# WiFi.net
KiCad netlist of a schematic drawn in Altium Designer
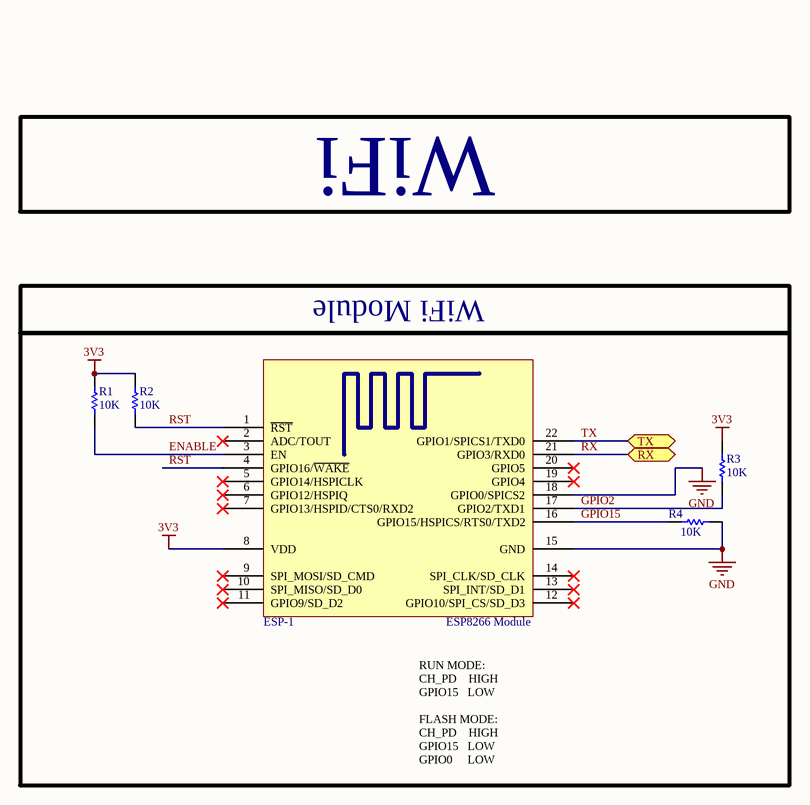
[diagram p0: WiFi.SchDoc]

(export (version "E")
  (design (tool "Eeschema 10.0.6"))
  (components
    (comp (ref "ESP-1")
      (value "ESP8266 Module")
      (footprint "PCBComponent")
      (libsource (lib "BG Vault") (part "ESP-12E-A.4"))
    )
    (comp (ref "R1")
      (value "10K")
      (footprint "RESC0805(2012)_L")
      (description "10K 0.125W 5% 0805 (2012 Metric)  SMD")
      (fields (field (name "POWER") "0.125 W") (field (name "TOLERANCE") "5 %"))
      (libsource (lib "Altium Content Vault") (part "CMP-1013-00098-1"))
    )
    (comp (ref "R2")
      (value "10K")
      (footprint "RESC0805(2012)_L")
      (description "10K 0.125W 5% 0805 (2012 Metric)  SMD")
      (fields (field (name "POWER") "0.125 W") (field (name "TOLERANCE") "5 %"))
      (libsource (lib "Altium Content Vault") (part "CMP-1013-00098-1"))
    )
    (comp (ref "R3")
      (value "10K")
      (footprint "RESC0805(2012)_L")
      (description "10K 0.125W 5% 0805 (2012 Metric)  SMD")
      (fields (field (name "POWER") "0.125 W") (field (name "TOLERANCE") "5 %"))
      (libsource (lib "Altium Content Vault") (part "CMP-1013-00098-1"))
    )
    (comp (ref "R4")
      (value "10K")
      (footprint "RESC0805(2012)_L")
      (description "10K 0.125W 5% 0805 (2012 Metric)  SMD")
      (fields (field (name "POWER") "0.125 W") (field (name "TOLERANCE") "5 %"))
      (libsource (lib "Altium Content Vault") (part "CMP-1013-00098-1"))
    )
  )
  (nets
    (net (code "1") (name "/ENABLE") (class "Default")
      (node (ref "ESP-1") (pin "3") (pinfunction "EN_3") (pintype "passive"))
      (node (ref "R1") (pin "1") (pinfunction "1_1") (pintype "passive"))
    )
    (net (code "2") (name "/GPIO2") (class "Default")
      (node (ref "ESP-1") (pin "17") (pinfunction "GPIO2/TXD1_17") (pintype "passive"))
      (node (ref "R3") (pin "1") (pinfunction "1_1") (pintype "passive"))
    )
    (net (code "3") (name "/GPIO15") (class "Default")
      (node (ref "ESP-1") (pin "16") (pinfunction "GPIO15/HSPICS/RTS0/TXD2_16") (pintype "passive"))
      (node (ref "R4") (pin "2") (pinfunction "2_2") (pintype "passive"))
    )
    (net (code "4") (name "/RST") (class "Default")
      (node (ref "ESP-1") (pin "1") (pinfunction "~{RST}_1") (pintype "passive"))
      (node (ref "ESP-1") (pin "4") (pinfunction "GPIO16/~{WAKE}_4") (pintype "passive"))
      (node (ref "R2") (pin "1") (pinfunction "1_1") (pintype "passive"))
    )
    (net (code "5") (name "/RX") (class "Default")
      (node (ref "ESP-1") (pin "21") (pinfunction "GPIO3/RXD0_21") (pintype "passive"))
    )
    (net (code "6") (name "/TX") (class "Default")
      (node (ref "ESP-1") (pin "22") (pinfunction "GPIO1/SPICS1/TXD0_22") (pintype "passive"))
    )
    (net (code "7") (name "3V3") (class "Default")
      (node (ref "ESP-1") (pin "8") (pinfunction "VDD_8") (pintype "passive"))
      (node (ref "R1") (pin "2") (pinfunction "2_2") (pintype "passive"))
      (node (ref "R2") (pin "2") (pinfunction "2_2") (pintype "passive"))
      (node (ref "R3") (pin "2") (pinfunction "2_2") (pintype "passive"))
    )
    (net (code "8") (name "GND") (class "Default")
      (node (ref "ESP-1") (pin "15") (pinfunction "GND_15") (pintype "passive"))
      (node (ref "ESP-1") (pin "18") (pinfunction "GPIO0/SPICS2_18") (pintype "passive"))
      (node (ref "R4") (pin "1") (pinfunction "1_1") (pintype "passive"))
    )
    (net (code "9") (name "unconnected-(ESP-1-ADC{slash}TOUT-Pad2)") (class "Default")
      (node (ref "ESP-1") (pin "2") (pinfunction "ADC/TOUT_2") (pintype "passive+no_connect"))
    )
    (net (code "10") (name "unconnected-(ESP-1-GPIO4-Pad19)") (class "Default")
      (node (ref "ESP-1") (pin "19") (pinfunction "GPIO4_19") (pintype "passive+no_connect"))
    )
    (net (code "11") (name "unconnected-(ESP-1-GPIO5-Pad20)") (class "Default")
      (node (ref "ESP-1") (pin "20") (pinfunction "GPIO5_20") (pintype "passive+no_connect"))
    )
    (net (code "12") (name "unconnected-(ESP-1-GPIO9{slash}SD_D2-Pad11)") (class "Default")
      (node (ref "ESP-1") (pin "11") (pinfunction "GPIO9/SD_D2_11") (pintype "passive+no_connect"))
    )
    (net (code "13") (name "unconnected-(ESP-1-GPIO10{slash}SPI_CS{slash}SD_D3-Pad12)") (class "Default")
      (node (ref "ESP-1") (pin "12") (pinfunction "GPIO10/SPI_CS/SD_D3_12") (pintype "passive+no_connect"))
    )
    (net (code "14") (name "unconnected-(ESP-1-GPIO12{slash}HSPIQ-Pad6)") (class "Default")
      (node (ref "ESP-1") (pin "6") (pinfunction "GPIO12/HSPIQ_6") (pintype "passive+no_connect"))
    )
    (net (code "15") (name "unconnected-(ESP-1-GPIO13{slash}HSPID{slash}CTS0{slash}RXD2-Pad7)") (class "Default")
      (node (ref "ESP-1") (pin "7") (pinfunction "GPIO13/HSPID/CTS0/RXD2_7") (pintype "passive+no_connect"))
    )
    (net (code "16") (name "unconnected-(ESP-1-GPIO14{slash}HSPICLK-Pad5)") (class "Default")
      (node (ref "ESP-1") (pin "5") (pinfunction "GPIO14/HSPICLK_5") (pintype "passive+no_connect"))
    )
    (net (code "17") (name "unconnected-(ESP-1-SPI_CLK{slash}SD_CLK-Pad14)") (class "Default")
      (node (ref "ESP-1") (pin "14") (pinfunction "SPI_CLK/SD_CLK_14") (pintype "passive+no_connect"))
    )
    (net (code "18") (name "unconnected-(ESP-1-SPI_INT{slash}SD_D1-Pad13)") (class "Default")
      (node (ref "ESP-1") (pin "13") (pinfunction "SPI_INT/SD_D1_13") (pintype "passive+no_connect"))
    )
    (net (code "19") (name "unconnected-(ESP-1-SPI_MISO{slash}SD_D0-Pad10)") (class "Default")
      (node (ref "ESP-1") (pin "10") (pinfunction "SPI_MISO/SD_D0_10") (pintype "passive+no_connect"))
    )
    (net (code "20") (name "unconnected-(ESP-1-SPI_MOSI{slash}SD_CMD-Pad9)") (class "Default")
      (node (ref "ESP-1") (pin "9") (pinfunction "SPI_MOSI/SD_CMD_9") (pintype "passive+no_connect"))
    )
  )
)
